# SCH_catvalve.net
KiCad netlist of a schematic drawn in EasyEDA
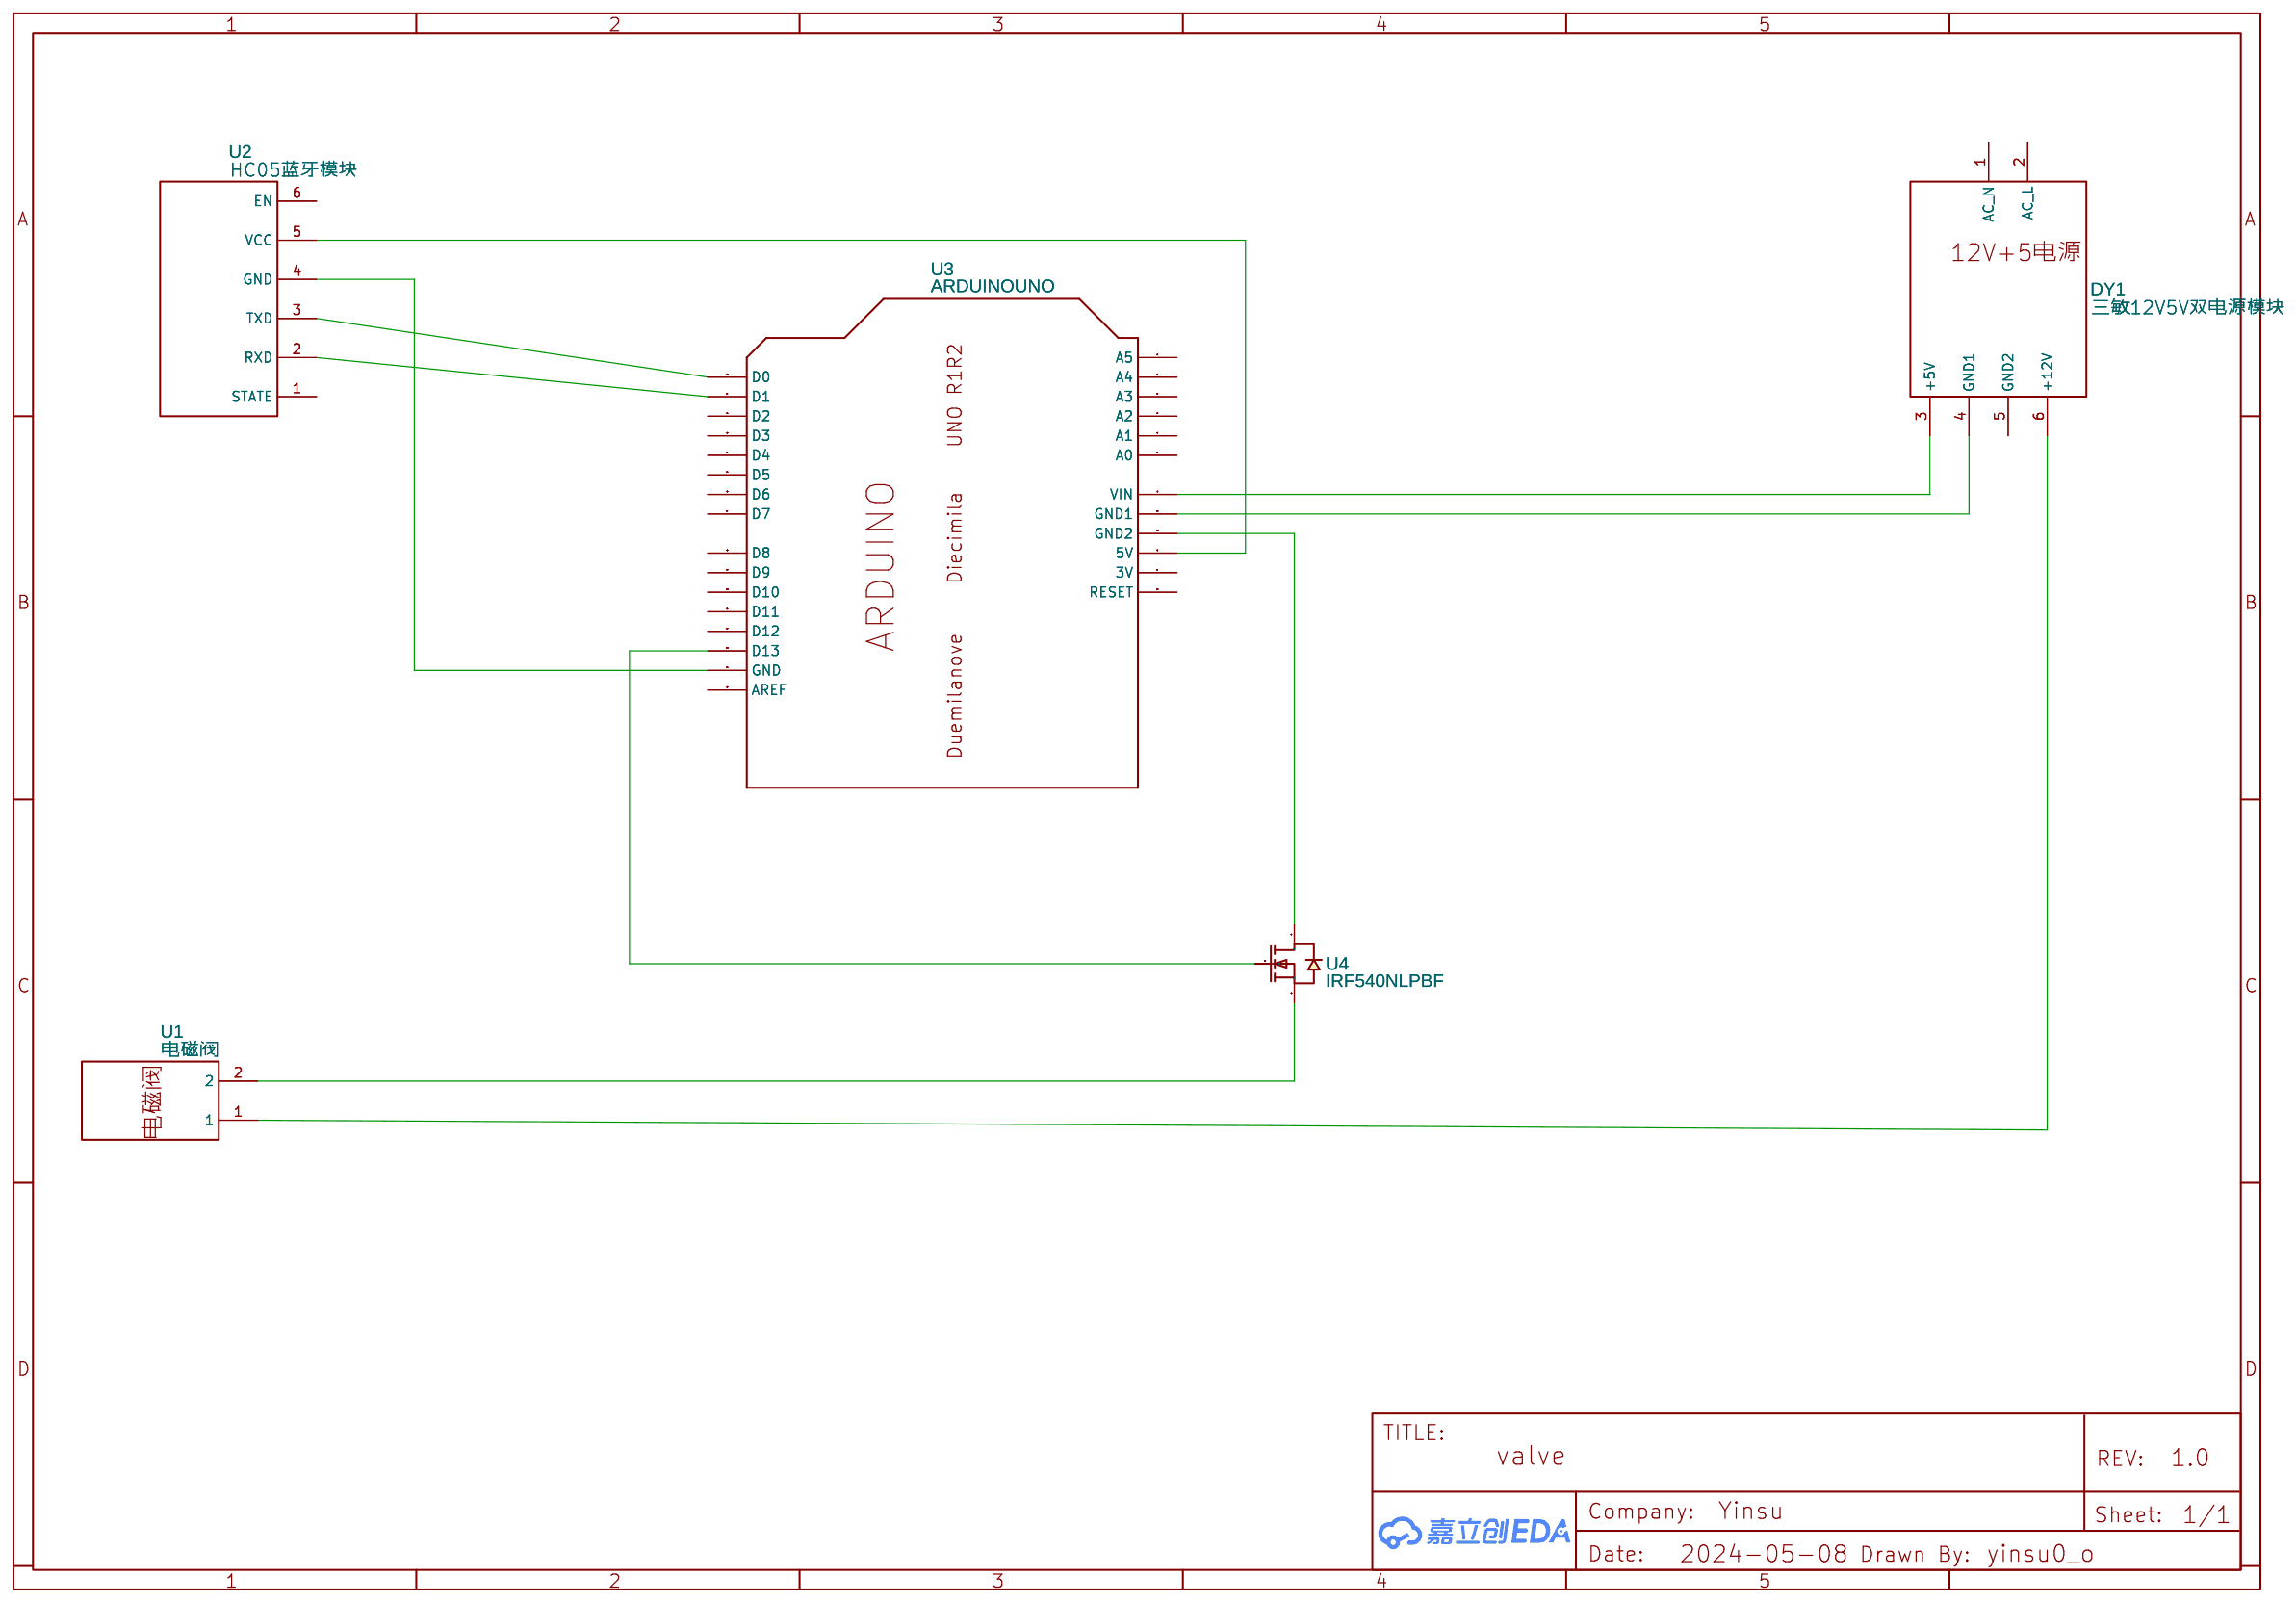
[diagram p0: schematic sheet]

(export (version "E")
  (design (tool "Eeschema 10.0.6"))
  (components
    (comp (ref "DY1") (value "三敏12V5V双电源模块") (libsource (lib "") (part "三敏12V5V双电源模块")))
    (comp (ref "U1") (value "电磁阀") (libsource (lib "") (part "电磁阀")))
    (comp (ref "U2") (value "HC05蓝牙模块") (libsource (lib "") (part "HC05")))
    (comp (ref "U3") (value "ARDUINOUNO") (libsource (lib "") (part "ARDUINOUNO")))
    (comp (ref "U4")
      (value "IRF540NLPBF")
      (fields (field (name "Manufacturer") "Infineon(英飞凌)"))
      (libsource (lib "") (part "IRF540NLPBF"))
    )
  )
  (nets
    (net (code "1") (name "Net-(DY1-+5V)") (class "Default")
      (node (ref "DY1") (pin "3") (pinfunction "+5V_3") (pintype "unspecified"))
      (node (ref "U3") (pin "VIN") (pinfunction "VIN_VIN") (pintype "unspecified"))
    )
    (net (code "2") (name "Net-(DY1-+12V)") (class "Default")
      (node (ref "DY1") (pin "6") (pinfunction "+12V_6") (pintype "unspecified"))
      (node (ref "U1") (pin "1") (pinfunction "1_1") (pintype "unspecified"))
    )
    (net (code "3") (name "Net-(DY1-GND1)") (class "Default")
      (node (ref "DY1") (pin "4") (pinfunction "GND1_4") (pintype "unspecified"))
      (node (ref "U3") (pin "GND1") (pinfunction "GND1_GND1") (pintype "unspecified"))
    )
    (net (code "4") (name "Net-(U2-GND)") (class "Default")
      (node (ref "U2") (pin "4") (pinfunction "GND_4") (pintype "unspecified"))
      (node (ref "U3") (pin "GND") (pinfunction "GND_GND") (pintype "unspecified"))
    )
    (net (code "5") (name "Net-(U2-RXD)") (class "Default")
      (node (ref "U2") (pin "2") (pinfunction "RXD_2") (pintype "unspecified"))
      (node (ref "U3") (pin "D1") (pinfunction "D1_D1") (pintype "unspecified"))
    )
    (net (code "6") (name "Net-(U2-TXD)") (class "Default")
      (node (ref "U2") (pin "3") (pinfunction "TXD_3") (pintype "unspecified"))
      (node (ref "U3") (pin "D0") (pinfunction "D0_D0") (pintype "unspecified"))
    )
    (net (code "7") (name "Net-(U2-VCC)") (class "Default")
      (node (ref "U2") (pin "5") (pinfunction "VCC_5") (pintype "unspecified"))
      (node (ref "U3") (pin "5V") (pinfunction "5V_5V") (pintype "unspecified"))
    )
    (net (code "8") (name "Net-(U4-D)") (class "Default")
      (node (ref "U3") (pin "GND2") (pinfunction "GND2_GND2") (pintype "unspecified"))
      (node (ref "U4") (pin "2") (pinfunction "D_2") (pintype "unspecified"))
    )
    (net (code "9") (name "Net-(U4-G)") (class "Default")
      (node (ref "U3") (pin "D13") (pinfunction "D13_D13") (pintype "unspecified"))
      (node (ref "U4") (pin "1") (pinfunction "G_1") (pintype "unspecified"))
    )
    (net (code "10") (name "Net-(U4-S)") (class "Default")
      (node (ref "U1") (pin "2") (pinfunction "2_2") (pintype "unspecified"))
      (node (ref "U4") (pin "3") (pinfunction "S_3") (pintype "unspecified"))
    )
    (net (code "11") (name "unconnected-(DY1-AC_L-Pad2)") (class "Default")
      (node (ref "DY1") (pin "2") (pinfunction "AC_L_2") (pintype "unspecified"))
    )
    (net (code "12") (name "unconnected-(DY1-AC_N-Pad1)") (class "Default")
      (node (ref "DY1") (pin "1") (pinfunction "AC_N_1") (pintype "unspecified"))
    )
    (net (code "13") (name "unconnected-(DY1-GND2-Pad5)") (class "Default")
      (node (ref "DY1") (pin "5") (pinfunction "GND2_5") (pintype "unspecified"))
    )
    (net (code "14") (name "unconnected-(U2-EN-Pad6)") (class "Default")
      (node (ref "U2") (pin "6") (pinfunction "EN_6") (pintype "unspecified"))
    )
    (net (code "15") (name "unconnected-(U2-STATE-Pad1)") (class "Default")
      (node (ref "U2") (pin "1") (pinfunction "STATE_1") (pintype "unspecified"))
    )
    (net (code "16") (name "unconnected-(U3-Pad3V)") (class "Default")
      (node (ref "U3") (pin "3V") (pinfunction "3V_3V") (pintype "unspecified"))
    )
    (net (code "17") (name "unconnected-(U3-PadA0)") (class "Default")
      (node (ref "U3") (pin "A0") (pinfunction "A0_A0") (pintype "unspecified"))
    )
    (net (code "18") (name "unconnected-(U3-PadA1)") (class "Default")
      (node (ref "U3") (pin "A1") (pinfunction "A1_A1") (pintype "unspecified"))
    )
    (net (code "19") (name "unconnected-(U3-PadA2)") (class "Default")
      (node (ref "U3") (pin "A2") (pinfunction "A2_A2") (pintype "unspecified"))
    )
    (net (code "20") (name "unconnected-(U3-PadA3)") (class "Default")
      (node (ref "U3") (pin "A3") (pinfunction "A3_A3") (pintype "unspecified"))
    )
    (net (code "21") (name "unconnected-(U3-PadA4)") (class "Default")
      (node (ref "U3") (pin "A4") (pinfunction "A4_A4") (pintype "unspecified"))
    )
    (net (code "22") (name "unconnected-(U3-PadA5)") (class "Default")
      (node (ref "U3") (pin "A5") (pinfunction "A5_A5") (pintype "unspecified"))
    )
    (net (code "23") (name "unconnected-(U3-PadAREF)") (class "Default")
      (node (ref "U3") (pin "AREF") (pinfunction "AREF_AREF") (pintype "unspecified"))
    )
    (net (code "24") (name "unconnected-(U3-PadD2)") (class "Default")
      (node (ref "U3") (pin "D2") (pinfunction "D2_D2") (pintype "unspecified"))
    )
    (net (code "25") (name "unconnected-(U3-PadD3)") (class "Default")
      (node (ref "U3") (pin "D3") (pinfunction "D3_D3") (pintype "unspecified"))
    )
    (net (code "26") (name "unconnected-(U3-PadD4)") (class "Default")
      (node (ref "U3") (pin "D4") (pinfunction "D4_D4") (pintype "unspecified"))
    )
    (net (code "27") (name "unconnected-(U3-PadD5)") (class "Default")
      (node (ref "U3") (pin "D5") (pinfunction "D5_D5") (pintype "unspecified"))
    )
    (net (code "28") (name "unconnected-(U3-PadD6)") (class "Default")
      (node (ref "U3") (pin "D6") (pinfunction "D6_D6") (pintype "unspecified"))
    )
    (net (code "29") (name "unconnected-(U3-PadD7)") (class "Default")
      (node (ref "U3") (pin "D7") (pinfunction "D7_D7") (pintype "unspecified"))
    )
    (net (code "30") (name "unconnected-(U3-PadD8)") (class "Default")
      (node (ref "U3") (pin "D8") (pinfunction "D8_D8") (pintype "unspecified"))
    )
    (net (code "31") (name "unconnected-(U3-PadD9)") (class "Default")
      (node (ref "U3") (pin "D9") (pinfunction "D9_D9") (pintype "unspecified"))
    )
    (net (code "32") (name "unconnected-(U3-PadD10)") (class "Default")
      (node (ref "U3") (pin "D10") (pinfunction "D10_D10") (pintype "unspecified"))
    )
    (net (code "33") (name "unconnected-(U3-PadD11)") (class "Default")
      (node (ref "U3") (pin "D11") (pinfunction "D11_D11") (pintype "unspecified"))
    )
    (net (code "34") (name "unconnected-(U3-PadD12)") (class "Default")
      (node (ref "U3") (pin "D12") (pinfunction "D12_D12") (pintype "unspecified"))
    )
    (net (code "35") (name "unconnected-(U3-PadRESET)") (class "Default")
      (node (ref "U3") (pin "RESET") (pinfunction "RESET_RESET") (pintype "unspecified"))
    )
  )
)
